# ELEC-URB-CANACC-R2_0A2.net
KiCad netlist of a schematic drawn in Altium Designer
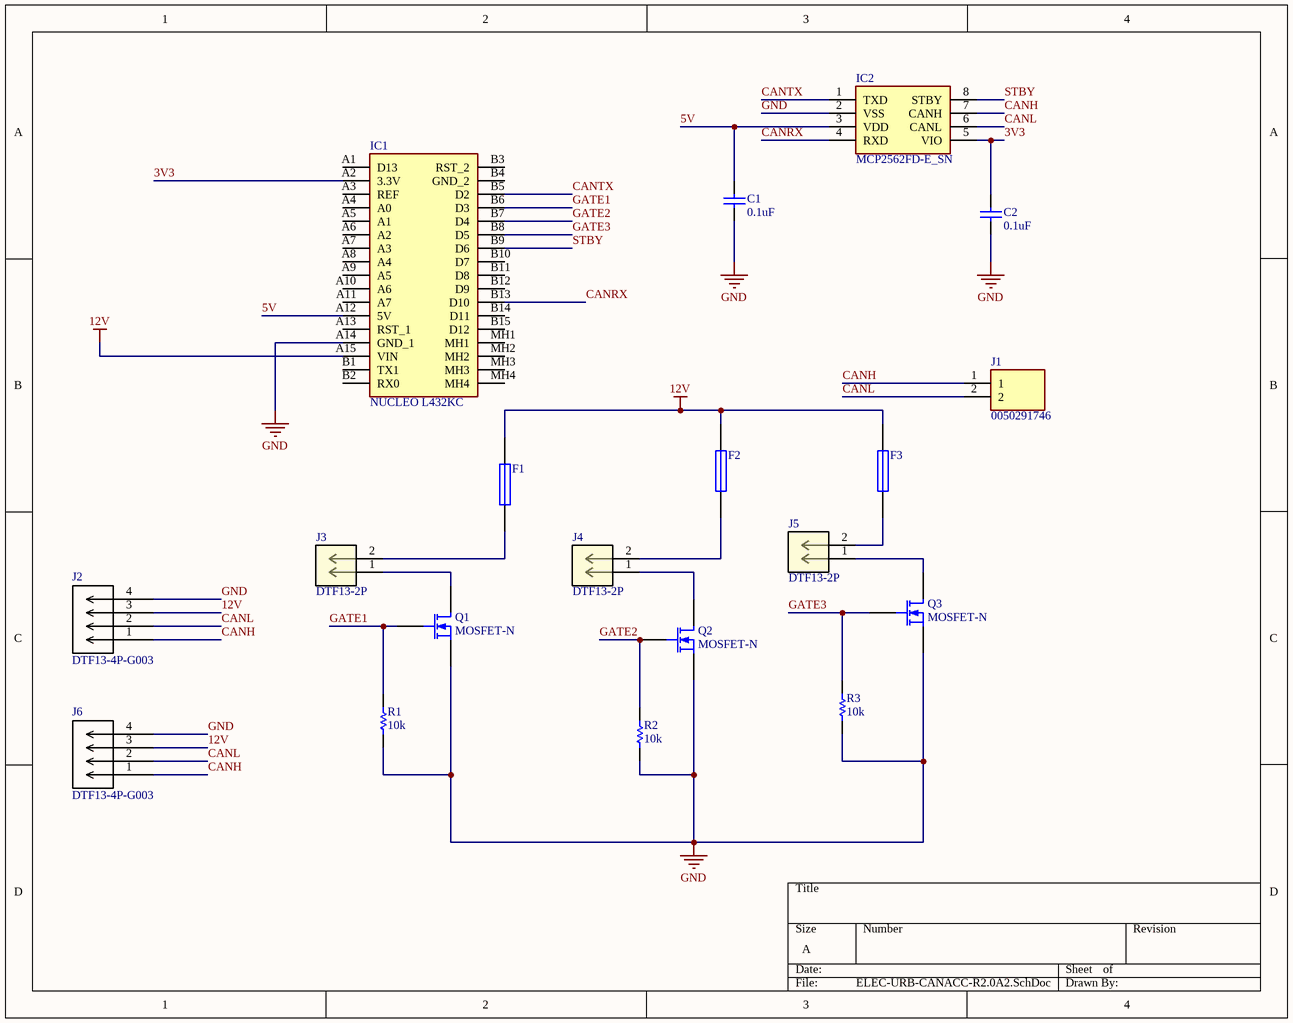
[diagram p0: ELEC-URB-CANACC-R2.0A2.SchDoc]

(export (version "E")
  (design (tool "Eeschema 10.0.6"))
  (components
    (comp (ref "C1")
      (value "0.1uF")
      (footprint "0603C")
      (description "Capacitor 0.1uF 16V")
      (libsource (lib "ELEC-URB-CANACC-R1.0A1") (part "Cap 0.1uF"))
    )
    (comp (ref "C2")
      (value "0.1uF")
      (footprint "0603C")
      (description "Capacitor 0.1uF 16V")
      (libsource (lib "ELEC-URB-CANACC-R1.0A1") (part "Cap 0.1uF"))
    )
    (comp (ref "F1")
      (value "Small Fuse")
      (footprint "SML FUSE HOLDER")
      (description "Fuse")
      (fields (field (name "PUBLISHER") "Altium Limited"))
      (libsource (lib "ELEC-URB-CANACC-R1.0A1") (part "Fuse 1"))
    )
    (comp (ref "F2")
      (value "Small Fuse")
      (footprint "SML FUSE HOLDER")
      (description "Fuse")
      (fields (field (name "PUBLISHER") "Altium Limited"))
      (libsource (lib "ELEC-URB-CANACC-R1.0A1") (part "Fuse 1"))
    )
    (comp (ref "F3")
      (value "Small Fuse")
      (footprint "SML FUSE HOLDER")
      (description "Fuse")
      (fields (field (name "PUBLISHER") "Altium Limited"))
      (libsource (lib "ELEC-URB-CANACC-R1.0A1") (part "Fuse 1"))
    )
    (comp (ref "IC1")
      (value "NUCLEO L432KC")
      (footprint "SamacSys:ABX00028")
      (description "Integrated Circuit")
      (fields
        (field (name "MANUFACTURER_PART_NUMBER") "ABX00028")
        (field (name "MOUSER PART NUMBER") "782-ABX00028")
      )
      (libsource (lib "ELEC-URB-CANACC-R1.0A1") (part "NUCLEO L432KC Arduino Nano Pinout"))
    )
    (comp (ref "IC2")
      (value "MCP2562FD-E_SN")
      (footprint "SamacSys:SOIC127P600X175-8N")
      (description "Integrated Circuit")
      (fields
        (field (name "MANUFACTURER_PART_NUMBER") "MCP2562FD-E/SN")
        (field (name "MOUSER PART NUMBER") "579-MCP2562FD-E/SN")
      )
      (libsource (lib "ELEC-URB-CANACC-R1.0A1") (part "MCP2562FD-E_SN"))
    )
    (comp (ref "J1")
      (value "0050291746")
      (footprint "SamacSys:SHDR2W87P0X254_1X2_493X635X1044P")
      (description "Connector")
      (libsource (lib "*") (part "0050291746"))
    )
    (comp (ref "J2")
      (value "DTF13-4P-G003")
      (footprint "CONN4_DTF13-4P")
      (description "DTF RECP ASM")
      (fields (field (name "COPYRIGHT") "Copyright (C) 2016 Accelerated Designs. All rights reserved"))
      (libsource (lib "ELEC-URB-CANACC-R1.0A1") (part "DTF13-4P-G003"))
    )
    (comp (ref "J3")
      (value "DTF13-2P")
      (footprint "CONN2_DTF13-2P")
      (description "DTF RECP ASM")
      (fields (field (name "COPYRIGHT") "Copyright (C) 2016 Accelerated Designs. All rights reserved"))
      (libsource (lib "ELEC-URB-CANACC-R1.0A1") (part "DTF13-2P"))
    )
    (comp (ref "J4")
      (value "DTF13-2P")
      (footprint "CONN2_DTF13-2P")
      (description "DTF RECP ASM")
      (fields (field (name "COPYRIGHT") "Copyright (C) 2016 Accelerated Designs. All rights reserved"))
      (libsource (lib "ELEC-URB-CANACC-R1.0A1") (part "DTF13-2P"))
    )
    (comp (ref "J5")
      (value "DTF13-2P")
      (footprint "CONN2_DTF13-2P")
      (description "DTF RECP ASM")
      (fields (field (name "COPYRIGHT") "Copyright (C) 2016 Accelerated Designs. All rights reserved"))
      (libsource (lib "ELEC-URB-CANACC-R1.0A1") (part "DTF13-2P"))
    )
    (comp (ref "J6")
      (value "DTF13-4P-G003")
      (footprint "CONN4_DTF13-4P")
      (description "DTF RECP ASM")
      (fields (field (name "COPYRIGHT") "Copyright (C) 2016 Accelerated Designs. All rights reserved"))
      (libsource (lib "ELEC-URB-CANACC-R1.0A1") (part "DTF13-4P-G003"))
    )
    (comp (ref "Q1")
      (value "MOSFET-N")
      (footprint "Diode Mosfet")
      (description "N-Channel MOSFET")
      (fields (field (name "PUBLISHER") "Altium Limited"))
      (libsource (lib "ELEC-URB-CANACC-R1.0A1") (part "MOSFET-N"))
    )
    (comp (ref "Q2")
      (value "MOSFET-N")
      (footprint "Diode Mosfet")
      (description "N-Channel MOSFET")
      (fields (field (name "PUBLISHER") "Altium Limited"))
      (libsource (lib "ELEC-URB-CANACC-R1.0A1") (part "MOSFET-N"))
    )
    (comp (ref "Q3")
      (value "MOSFET-N")
      (footprint "Diode Mosfet")
      (description "N-Channel MOSFET")
      (fields (field (name "PUBLISHER") "Altium Limited"))
      (libsource (lib "ELEC-URB-CANACC-R1.0A1") (part "MOSFET-N"))
    )
    (comp (ref "R1")
      (value "10k")
      (footprint "0603R")
      (description "Resistor 10K")
      (libsource (lib "ELEC-URB-CANACC-R1.0A1") (part "Res 10k"))
    )
    (comp (ref "R2")
      (value "10k")
      (footprint "0603R")
      (description "Resistor 10K")
      (libsource (lib "ELEC-URB-CANACC-R1.0A1") (part "Res 10k"))
    )
    (comp (ref "R3")
      (value "10k")
      (footprint "0603R")
      (description "Resistor 10K")
      (libsource (lib "ELEC-URB-CANACC-R1.0A1") (part "Res 10k"))
    )
  )
  (nets
    (net (code "1") (name "/3V3") (class "Default")
      (node (ref "C2") (pin "2") (pinfunction "2_2") (pintype "passive"))
      (node (ref "IC1") (pin "A2") (pinfunction "3.3V_A2") (pintype "passive"))
      (node (ref "IC2") (pin "5") (pinfunction "VIO_5") (pintype "passive"))
    )
    (net (code "2") (name "/5V") (class "Default")
      (node (ref "C1") (pin "1") (pinfunction "1_1") (pintype "passive"))
      (node (ref "IC1") (pin "A12") (pinfunction "5V_A12") (pintype "passive"))
      (node (ref "IC2") (pin "3") (pinfunction "VDD_3") (pintype "passive"))
    )
    (net (code "3") (name "/CANH") (class "Default")
      (node (ref "IC2") (pin "7") (pinfunction "CANH_7") (pintype "passive"))
      (node (ref "J1") (pin "1") (pinfunction "1_1") (pintype "passive"))
      (node (ref "J2") (pin "1") (pinfunction "1_1") (pintype "passive"))
      (node (ref "J6") (pin "1") (pinfunction "1_1") (pintype "passive"))
    )
    (net (code "4") (name "/CANL") (class "Default")
      (node (ref "IC2") (pin "6") (pinfunction "CANL_6") (pintype "passive"))
      (node (ref "J1") (pin "2") (pinfunction "2_2") (pintype "passive"))
      (node (ref "J2") (pin "2") (pinfunction "2_2") (pintype "passive"))
      (node (ref "J6") (pin "2") (pinfunction "2_2") (pintype "passive"))
    )
    (net (code "5") (name "/CANRX") (class "Default")
      (node (ref "IC1") (pin "B13") (pinfunction "D10_B13") (pintype "passive"))
      (node (ref "IC2") (pin "4") (pinfunction "RXD_4") (pintype "passive"))
    )
    (net (code "6") (name "/CANTX") (class "Default")
      (node (ref "IC1") (pin "B5") (pinfunction "D2_B5") (pintype "passive"))
      (node (ref "IC2") (pin "1") (pinfunction "TXD_1") (pintype "passive"))
    )
    (net (code "7") (name "/GATE1") (class "Default")
      (node (ref "IC1") (pin "B6") (pinfunction "D3_B6") (pintype "passive"))
      (node (ref "Q1") (pin "2") (pinfunction "G_2") (pintype "passive"))
      (node (ref "R1") (pin "2") (pinfunction "2_2") (pintype "passive"))
    )
    (net (code "8") (name "/GATE2") (class "Default")
      (node (ref "IC1") (pin "B7") (pinfunction "D4_B7") (pintype "passive"))
      (node (ref "Q2") (pin "2") (pinfunction "G_2") (pintype "passive"))
      (node (ref "R2") (pin "2") (pinfunction "2_2") (pintype "passive"))
    )
    (net (code "9") (name "/GATE3") (class "Default")
      (node (ref "IC1") (pin "B8") (pinfunction "D5_B8") (pintype "passive"))
      (node (ref "Q3") (pin "2") (pinfunction "G_2") (pintype "passive"))
      (node (ref "R3") (pin "2") (pinfunction "2_2") (pintype "passive"))
    )
    (net (code "10") (name "/STBY") (class "Default")
      (node (ref "IC1") (pin "B9") (pinfunction "D6_B9") (pintype "passive"))
      (node (ref "IC2") (pin "8") (pinfunction "STBY_8") (pintype "passive"))
    )
    (net (code "11") (name "12V") (class "Default")
      (node (ref "F1") (pin "1") (pinfunction "1_1") (pintype "passive"))
      (node (ref "F2") (pin "2") (pinfunction "2_2") (pintype "passive"))
      (node (ref "F3") (pin "2") (pinfunction "2_2") (pintype "passive"))
      (node (ref "IC1") (pin "A15") (pinfunction "VIN_A15") (pintype "passive"))
      (node (ref "J2") (pin "3") (pinfunction "3_3") (pintype "passive"))
      (node (ref "J6") (pin "3") (pinfunction "3_3") (pintype "passive"))
    )
    (net (code "12") (name "GND") (class "Default")
      (node (ref "C1") (pin "2") (pinfunction "2_2") (pintype "passive"))
      (node (ref "C2") (pin "1") (pinfunction "1_1") (pintype "passive"))
      (node (ref "IC1") (pin "A14") (pinfunction "GND_1_A14") (pintype "passive"))
      (node (ref "IC2") (pin "2") (pinfunction "VSS_2") (pintype "passive"))
      (node (ref "J2") (pin "4") (pinfunction "4_4") (pintype "passive"))
      (node (ref "J6") (pin "4") (pinfunction "4_4") (pintype "passive"))
      (node (ref "Q1") (pin "3") (pinfunction "S_3") (pintype "passive"))
      (node (ref "Q2") (pin "3") (pinfunction "S_3") (pintype "passive"))
      (node (ref "Q3") (pin "3") (pinfunction "S_3") (pintype "passive"))
      (node (ref "R1") (pin "1") (pinfunction "1_1") (pintype "passive"))
      (node (ref "R2") (pin "1") (pinfunction "1_1") (pintype "passive"))
      (node (ref "R3") (pin "1") (pinfunction "1_1") (pintype "passive"))
    )
    (net (code "13") (name "Net-(F1-Pad2)") (class "Default")
      (node (ref "F1") (pin "2") (pinfunction "2_2") (pintype "passive"))
      (node (ref "J3") (pin "2") (pinfunction "2_2") (pintype "passive"))
    )
    (net (code "14") (name "Net-(F2-Pad1)") (class "Default")
      (node (ref "F2") (pin "1") (pinfunction "1_1") (pintype "passive"))
      (node (ref "J4") (pin "2") (pinfunction "2_2") (pintype "passive"))
    )
    (net (code "15") (name "Net-(F3-Pad1)") (class "Default")
      (node (ref "F3") (pin "1") (pinfunction "1_1") (pintype "passive"))
      (node (ref "J5") (pin "2") (pinfunction "2_2") (pintype "passive"))
    )
    (net (code "16") (name "Net-(Q1-D)") (class "Default")
      (node (ref "J3") (pin "1") (pinfunction "1_1") (pintype "passive"))
      (node (ref "Q1") (pin "1") (pinfunction "D_1") (pintype "passive"))
    )
    (net (code "17") (name "Net-(Q2-D)") (class "Default")
      (node (ref "J4") (pin "1") (pinfunction "1_1") (pintype "passive"))
      (node (ref "Q2") (pin "1") (pinfunction "D_1") (pintype "passive"))
    )
    (net (code "18") (name "Net-(Q3-D)") (class "Default")
      (node (ref "J5") (pin "1") (pinfunction "1_1") (pintype "passive"))
      (node (ref "Q3") (pin "1") (pinfunction "D_1") (pintype "passive"))
    )
    (net (code "19") (name "unconnected-(IC1-A0-PadA4)") (class "Default")
      (node (ref "IC1") (pin "A4") (pinfunction "A0_A4") (pintype "passive"))
    )
    (net (code "20") (name "unconnected-(IC1-A1-PadA5)") (class "Default")
      (node (ref "IC1") (pin "A5") (pinfunction "A1_A5") (pintype "passive"))
    )
    (net (code "21") (name "unconnected-(IC1-A2-PadA6)") (class "Default")
      (node (ref "IC1") (pin "A6") (pinfunction "A2_A6") (pintype "passive"))
    )
    (net (code "22") (name "unconnected-(IC1-A3-PadA7)") (class "Default")
      (node (ref "IC1") (pin "A7") (pinfunction "A3_A7") (pintype "passive"))
    )
    (net (code "23") (name "unconnected-(IC1-A4-PadA8)") (class "Default")
      (node (ref "IC1") (pin "A8") (pinfunction "A4_A8") (pintype "passive"))
    )
    (net (code "24") (name "unconnected-(IC1-A5-PadA9)") (class "Default")
      (node (ref "IC1") (pin "A9") (pinfunction "A5_A9") (pintype "passive"))
    )
    (net (code "25") (name "unconnected-(IC1-A6-PadA10)") (class "Default")
      (node (ref "IC1") (pin "A10") (pinfunction "A6_A10") (pintype "passive"))
    )
    (net (code "26") (name "unconnected-(IC1-A7-PadA11)") (class "Default")
      (node (ref "IC1") (pin "A11") (pinfunction "A7_A11") (pintype "passive"))
    )
    (net (code "27") (name "unconnected-(IC1-D7-PadB10)") (class "Default")
      (node (ref "IC1") (pin "B10") (pinfunction "D7_B10") (pintype "passive"))
    )
    (net (code "28") (name "unconnected-(IC1-D8-PadB11)") (class "Default")
      (node (ref "IC1") (pin "B11") (pinfunction "D8_B11") (pintype "passive"))
    )
    (net (code "29") (name "unconnected-(IC1-D9-PadB12)") (class "Default")
      (node (ref "IC1") (pin "B12") (pinfunction "D9_B12") (pintype "passive"))
    )
    (net (code "30") (name "unconnected-(IC1-D11-PadB14)") (class "Default")
      (node (ref "IC1") (pin "B14") (pinfunction "D11_B14") (pintype "passive"))
    )
    (net (code "31") (name "unconnected-(IC1-D12-PadB15)") (class "Default")
      (node (ref "IC1") (pin "B15") (pinfunction "D12_B15") (pintype "passive"))
    )
    (net (code "32") (name "unconnected-(IC1-D13-PadA1)") (class "Default")
      (node (ref "IC1") (pin "A1") (pinfunction "D13_A1") (pintype "passive"))
    )
    (net (code "33") (name "unconnected-(IC1-GND_2-PadB4)") (class "Default")
      (node (ref "IC1") (pin "B4") (pinfunction "GND_2_B4") (pintype "passive"))
    )
    (net (code "34") (name "unconnected-(IC1-PadMH1)") (class "Default")
      (node (ref "IC1") (pin "MH1") (pinfunction "MH1_MH1") (pintype "passive"))
    )
    (net (code "35") (name "unconnected-(IC1-PadMH2)") (class "Default")
      (node (ref "IC1") (pin "MH2") (pinfunction "MH2_MH2") (pintype "passive"))
    )
    (net (code "36") (name "unconnected-(IC1-PadMH3)") (class "Default")
      (node (ref "IC1") (pin "MH3") (pinfunction "MH3_MH3") (pintype "passive"))
    )
    (net (code "37") (name "unconnected-(IC1-PadMH4)") (class "Default")
      (node (ref "IC1") (pin "MH4") (pinfunction "MH4_MH4") (pintype "passive"))
    )
    (net (code "38") (name "unconnected-(IC1-REF-PadA3)") (class "Default")
      (node (ref "IC1") (pin "A3") (pinfunction "REF_A3") (pintype "passive"))
    )
    (net (code "39") (name "unconnected-(IC1-RST_1-PadA13)") (class "Default")
      (node (ref "IC1") (pin "A13") (pinfunction "RST_1_A13") (pintype "passive"))
    )
    (net (code "40") (name "unconnected-(IC1-RST_2-PadB3)") (class "Default")
      (node (ref "IC1") (pin "B3") (pinfunction "RST_2_B3") (pintype "passive"))
    )
    (net (code "41") (name "unconnected-(IC1-RX0-PadB2)") (class "Default")
      (node (ref "IC1") (pin "B2") (pinfunction "RX0_B2") (pintype "passive"))
    )
    (net (code "42") (name "unconnected-(IC1-TX1-PadB1)") (class "Default")
      (node (ref "IC1") (pin "B1") (pinfunction "TX1_B1") (pintype "passive"))
    )
  )
)
